# Regulator.net
KiCad netlist of a schematic drawn in Altium Designer
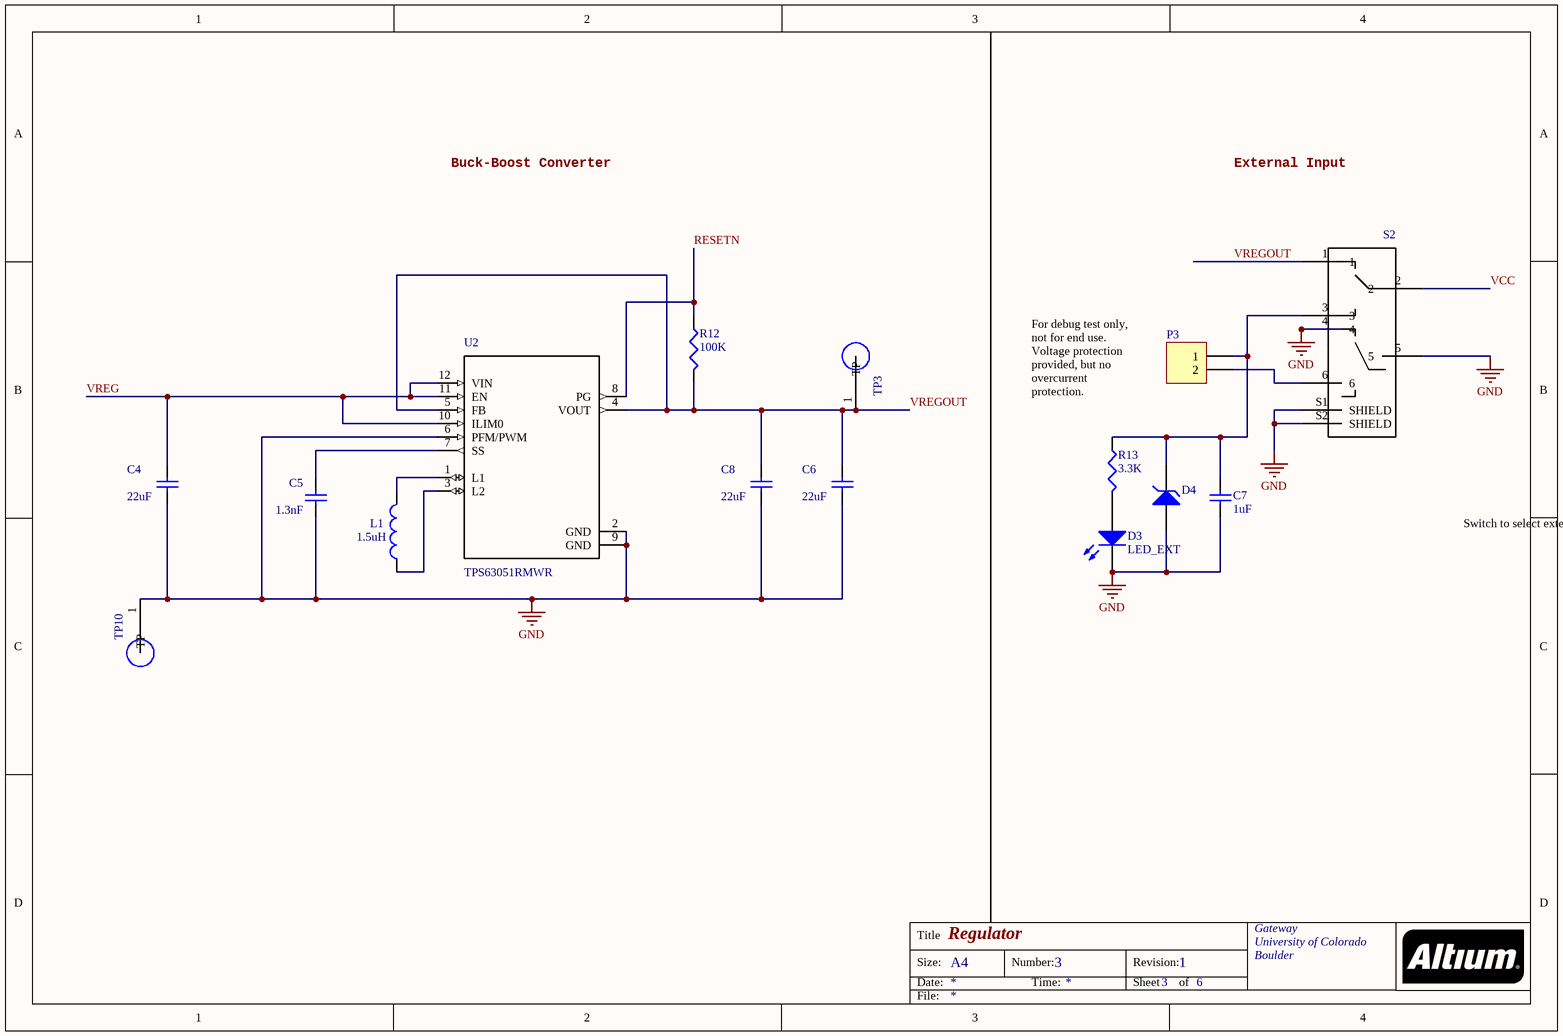
[diagram p0: Regulator.SchDoc]

(export (version "E")
  (design (tool "Eeschema 10.0.6"))
  (components
    (comp (ref "C4")
      (value "22uF")
      (footprint "1608[0603]")
      (description "CAP CER 22UF 10V X5R 0603")
      (fields
        (field (name "MANUFACTURER") "Samsung Electro-Mechanics")
        (field (name "MANUFACTURER PART NUMBER") "CL10A226MPCNUBE")
        (field (name "PUBLISHER") "Altium Limited")
      )
      (libsource (lib "Miscellaneous Devices") (part "Cap"))
    )
    (comp (ref "C5")
      (value "1.3nF")
      (footprint "1608[0603]")
      (description "CAP CER 1300PF 25V C0G/NP0 0603")
      (fields
        (field (name "MANUFACTURER") "KEMET")
        (field (name "MANUFACTURER PART NUMBER") "C0603C132J3GAC7867")
        (field (name "PUBLISHER") "Altium Limited")
      )
      (libsource (lib "Miscellaneous Devices") (part "Cap"))
    )
    (comp (ref "C6")
      (value "22uF")
      (footprint "1608[0603]")
      (description "CAP CER 22UF 10V X5R 0603")
      (fields
        (field (name "MANUFACTURER") "Samsung Electro-Mechanics")
        (field (name "MANUFACTURER PART NUMBER") "CL10A226MPCNUBE")
        (field (name "PUBLISHER") "Altium Limited")
      )
      (libsource (lib "Miscellaneous Devices") (part "Cap"))
    )
    (comp (ref "C7")
      (value "1uF")
      (footprint "1608[0603]")
      (description "CAP CER 1UF 10V X7R 0603")
      (fields
        (field (name "DIGI-KEY PART NUMBER") "1276-1946-1-ND")
        (field (name "MANUFACTURER") "Samsung Electro-Mechanics")
      )
      (libsource (lib "Miscellaneous Devices") (part "Cap Semi"))
    )
    (comp (ref "C8")
      (value "22uF")
      (footprint "1608[0603]")
      (description "CAP CER 22UF 10V X5R 0603")
      (fields
        (field (name "MANUFACTURER") "Samsung Electro-Mechanics")
        (field (name "MANUFACTURER PART NUMBER") "CL10A226MPCNUBE")
        (field (name "PUBLISHER") "Altium Limited")
      )
      (libsource (lib "Miscellaneous Devices") (part "Cap"))
    )
    (comp (ref "D3")
      (value "LED_EXT")
      (footprint "1608[0603]")
      (description "LED GREEN DIFFUSED 0603 SMD")
      (fields
        (field (name "DIGI-KEY PART NUMBER") "475-3118-1-ND")
        (field (name "MANUFACTURER") "OSRAM Opto Semiconductors Inc.")
      )
      (libsource (lib "Miscellaneous Devices") (part "LED2"))
    )
    (comp (ref "D4")
      (value "CZRQR3V3B-HF")
      (footprint "0402")
      (description "DIODE ZENER 3.3V 125MW 0402")
      (fields
        (field (name "DIGI-KEY PART NUMBER") "641-1682-1-ND")
        (field (name "MANUFACTURER") "Comchip Technology")
      )
      (libsource (lib "Miscellaneous Devices") (part "D Zener"))
    )
    (comp (ref "L1")
      (value "1.5uH")
      (footprint "1608[0603]")
      (description "FIXED IND 1.5UH 1.1A 213 MOHM")
      (fields
        (field (name "MANUFACTURER") "Murata Electronics North America")
        (field (name "MANUFACTURER PART NUMBER") "LQM18PN1R5MFHD")
        (field (name "PUBLISHER") "Altium Limited")
      )
      (libsource (lib "Miscellaneous Devices") (part "Inductor"))
    )
    (comp (ref "P3")
      (value "~")
      (footprint "HDR1X2")
      (description "Header, 2-Pin")
      (fields (field (name "PUBLISHER") "Altium Limited"))
      (libsource (lib "Miscellaneous Connectors") (part "Header 2"))
    )
    (comp (ref "R12")
      (value "100K")
      (footprint "1608[0603]")
      (description "RES SMD 100K OHM 0.1% 1/10W 0603")
      (fields
        (field (name "MANUFACTURER") "Susumu")
        (field (name "MANUFACTURER PART NUMBER") "RG1608P-104-B-T5")
        (field (name "PUBLISHER") "Altium Limited")
      )
      (libsource (lib "Miscellaneous Devices") (part "Res3"))
    )
    (comp (ref "R13")
      (value "3.3K")
      (footprint "1608[0603]")
      (description "RES SMD 3.3K OHM 5% 1/10W 0603")
      (fields
        (field (name "DIGI-KEY PART NUMBER") "P3.3KGCT-ND")
        (field (name "MANUFACTURER") "Panasonic Electronic Components")
      )
      (libsource (lib "Miscellaneous Devices") (part "Res3"))
    )
    (comp (ref "S2")
      (value "1825289-1")
      (footprint "SW_1825289-1_1825289-1(Primary)")
      (description "MHS22204=DPDT SL SW VERT AG")
      (fields
        (field (name "MANUFACTURER") "TE Connectivity")
        (field (name "DIGI-KEY PART NUMBER") "450-1572-ND")
      )
      (libsource (lib "1825289-1") (part "1825289-1"))
    )
    (comp (ref "TP3")
      (value "VREGOUT_TP")
      (footprint "TP380X203")
      (description "PC TEST POINT MINIATURE")
      (fields (field (name "MP") "5019") (field (name "DIGI-KEY_PART_NUMBER") "36-5019CT-ND"))
      (libsource (lib "5019") (part "5019"))
    )
    (comp (ref "TP10")
      (value "GND_TP")
      (footprint "TP380X203")
      (description "PC TEST POINT MINIATURE")
      (fields (field (name "MP") "5019") (field (name "DIGI-KEY_PART_NUMBER") "36-5019CT-ND"))
      (libsource (lib "5019") (part "5019"))
    )
    (comp (ref "U2")
      (value "TPS63051RMWR")
      (footprint "QFN50P250X250X100-12N")
      (description "Tiny Single Inductor Buck Boost Converter 12-VQFN -40 to 85")
      (fields
        (field (name "DIGI-KEY PART NUMBER") "296-42650-1-ND")
        (field (name "MANUFACTURER") "Texas Instruments")
      )
      (libsource (lib "TPS63051RMWR") (part "TPS63051RMWR"))
    )
  )
  (nets
    (net (code "1") (name "/RESETN") (class "Default")
      (node (ref "R12") (pin "1") (pinfunction "1_1") (pintype "passive"))
      (node (ref "U2") (pin "8") (pinfunction "PG_8") (pintype "output"))
    )
    (net (code "2") (name "/VCC") (class "Default")
      (node (ref "S2") (pin "2") (pinfunction "2_2") (pintype "passive"))
    )
    (net (code "3") (name "/VREG") (class "Default")
      (node (ref "C4") (pin "2") (pinfunction "2_2") (pintype "passive"))
      (node (ref "U2") (pin "10") (pinfunction "ILIM0_10") (pintype "input"))
      (node (ref "U2") (pin "11") (pinfunction "EN_11") (pintype "input"))
      (node (ref "U2") (pin "12") (pinfunction "VIN_12") (pintype "input"))
    )
    (net (code "4") (name "/VREGOUT") (class "Default")
      (node (ref "C6") (pin "2") (pinfunction "2_2") (pintype "passive"))
      (node (ref "C8") (pin "2") (pinfunction "2_2") (pintype "passive"))
      (node (ref "R12") (pin "2") (pinfunction "2_2") (pintype "passive"))
      (node (ref "S2") (pin "1") (pinfunction "1_1") (pintype "passive"))
      (node (ref "TP3") (pin "1") (pinfunction "TP_1") (pintype "passive"))
      (node (ref "U2") (pin "4") (pinfunction "VOUT_4") (pintype "output"))
      (node (ref "U2") (pin "5") (pinfunction "FB_5") (pintype "input"))
    )
    (net (code "5") (name "GND") (class "Default")
      (node (ref "C4") (pin "1") (pinfunction "1_1") (pintype "passive"))
      (node (ref "C5") (pin "1") (pinfunction "1_1") (pintype "passive"))
      (node (ref "C6") (pin "1") (pinfunction "1_1") (pintype "passive"))
      (node (ref "C7") (pin "1") (pinfunction "1_1") (pintype "passive"))
      (node (ref "C8") (pin "1") (pinfunction "1_1") (pintype "passive"))
      (node (ref "D3") (pin "2") (pinfunction "K_2") (pintype "passive"))
      (node (ref "D4") (pin "1") (pinfunction "A_1") (pintype "passive"))
      (node (ref "S2") (pin "4") (pinfunction "4_4") (pintype "passive"))
      (node (ref "S2") (pin "5") (pinfunction "5_5") (pintype "passive"))
      (node (ref "S2") (pin "S1") (pinfunction "SHIELD_S1") (pintype "passive"))
      (node (ref "S2") (pin "S2") (pinfunction "SHIELD_S2") (pintype "passive"))
      (node (ref "TP10") (pin "1") (pinfunction "TP_1") (pintype "passive"))
      (node (ref "U2") (pin "2") (pinfunction "GND_2") (pintype "power_in"))
      (node (ref "U2") (pin "6") (pinfunction "PFM/PWM_6") (pintype "input"))
      (node (ref "U2") (pin "9") (pinfunction "GND_9") (pintype "power_in"))
    )
    (net (code "6") (name "Net-(D3-A)") (class "Default")
      (node (ref "D3") (pin "1") (pinfunction "A_1") (pintype "passive"))
      (node (ref "R13") (pin "1") (pinfunction "1_1") (pintype "passive"))
    )
    (net (code "7") (name "Net-(D4-K)") (class "Default")
      (node (ref "C7") (pin "2") (pinfunction "2_2") (pintype "passive"))
      (node (ref "D4") (pin "2") (pinfunction "K_2") (pintype "passive"))
      (node (ref "P3") (pin "1") (pinfunction "1_1") (pintype "passive"))
      (node (ref "R13") (pin "2") (pinfunction "2_2") (pintype "passive"))
      (node (ref "S2") (pin "3") (pinfunction "3_3") (pintype "passive"))
    )
    (net (code "8") (name "Net-(P3-Pad2)") (class "Default")
      (node (ref "P3") (pin "2") (pinfunction "2_2") (pintype "passive"))
      (node (ref "S2") (pin "6") (pinfunction "6_6") (pintype "passive"))
    )
    (net (code "9") (name "Net-(U2-L1)") (class "Default")
      (node (ref "L1") (pin "2") (pinfunction "2_2") (pintype "passive"))
      (node (ref "U2") (pin "1") (pinfunction "L1_1") (pintype "bidirectional"))
    )
    (net (code "10") (name "Net-(U2-L2)") (class "Default")
      (node (ref "L1") (pin "1") (pinfunction "1_1") (pintype "passive"))
      (node (ref "U2") (pin "3") (pinfunction "L2_3") (pintype "bidirectional"))
    )
    (net (code "11") (name "Net-(U2-SS)") (class "Default")
      (node (ref "C5") (pin "2") (pinfunction "2_2") (pintype "passive"))
      (node (ref "U2") (pin "7") (pinfunction "SS_7") (pintype "output"))
    )
  )
)
